# Dual_TPA6120_V0001.net
KiCad netlist of a schematic drawn in EAGLE
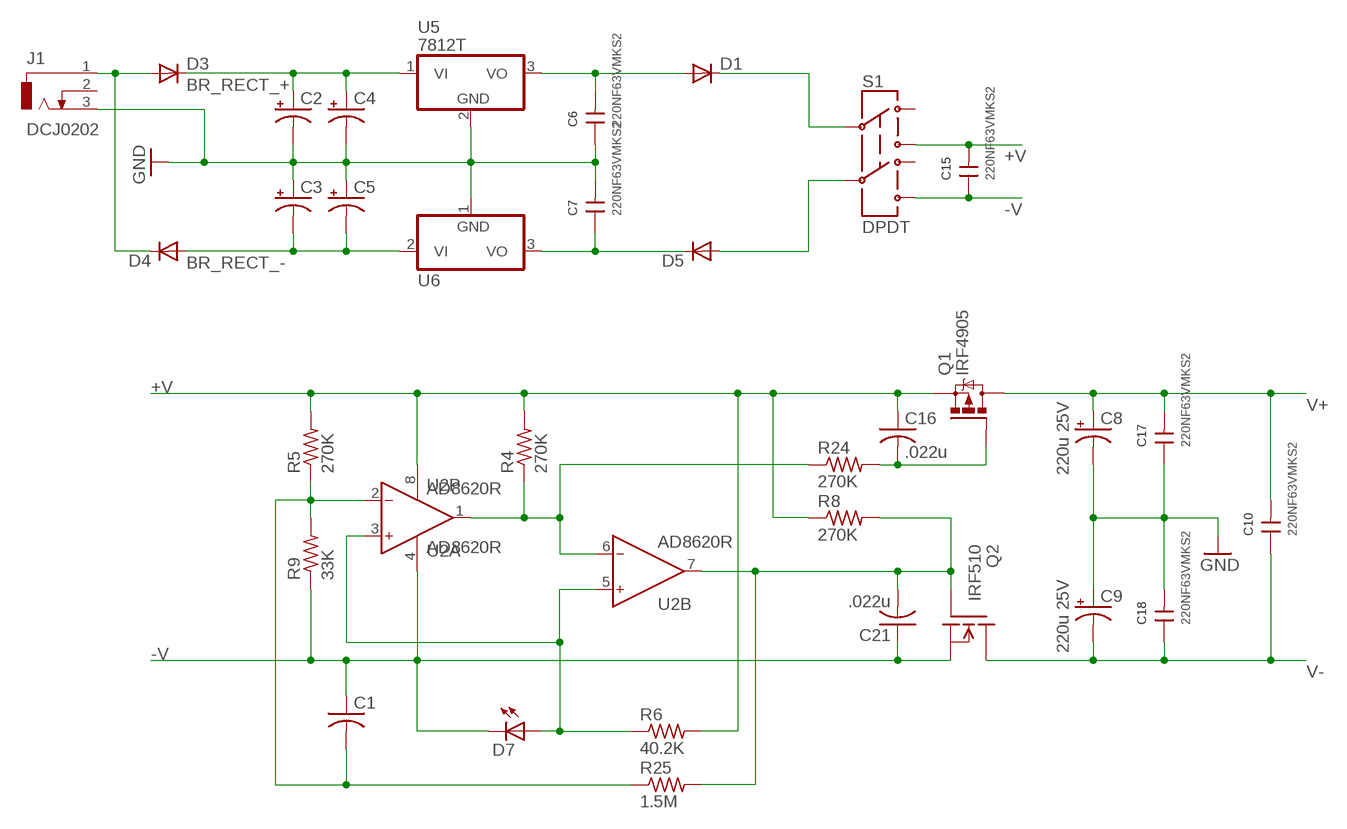
[diagram p0: schematic, sheet 1]
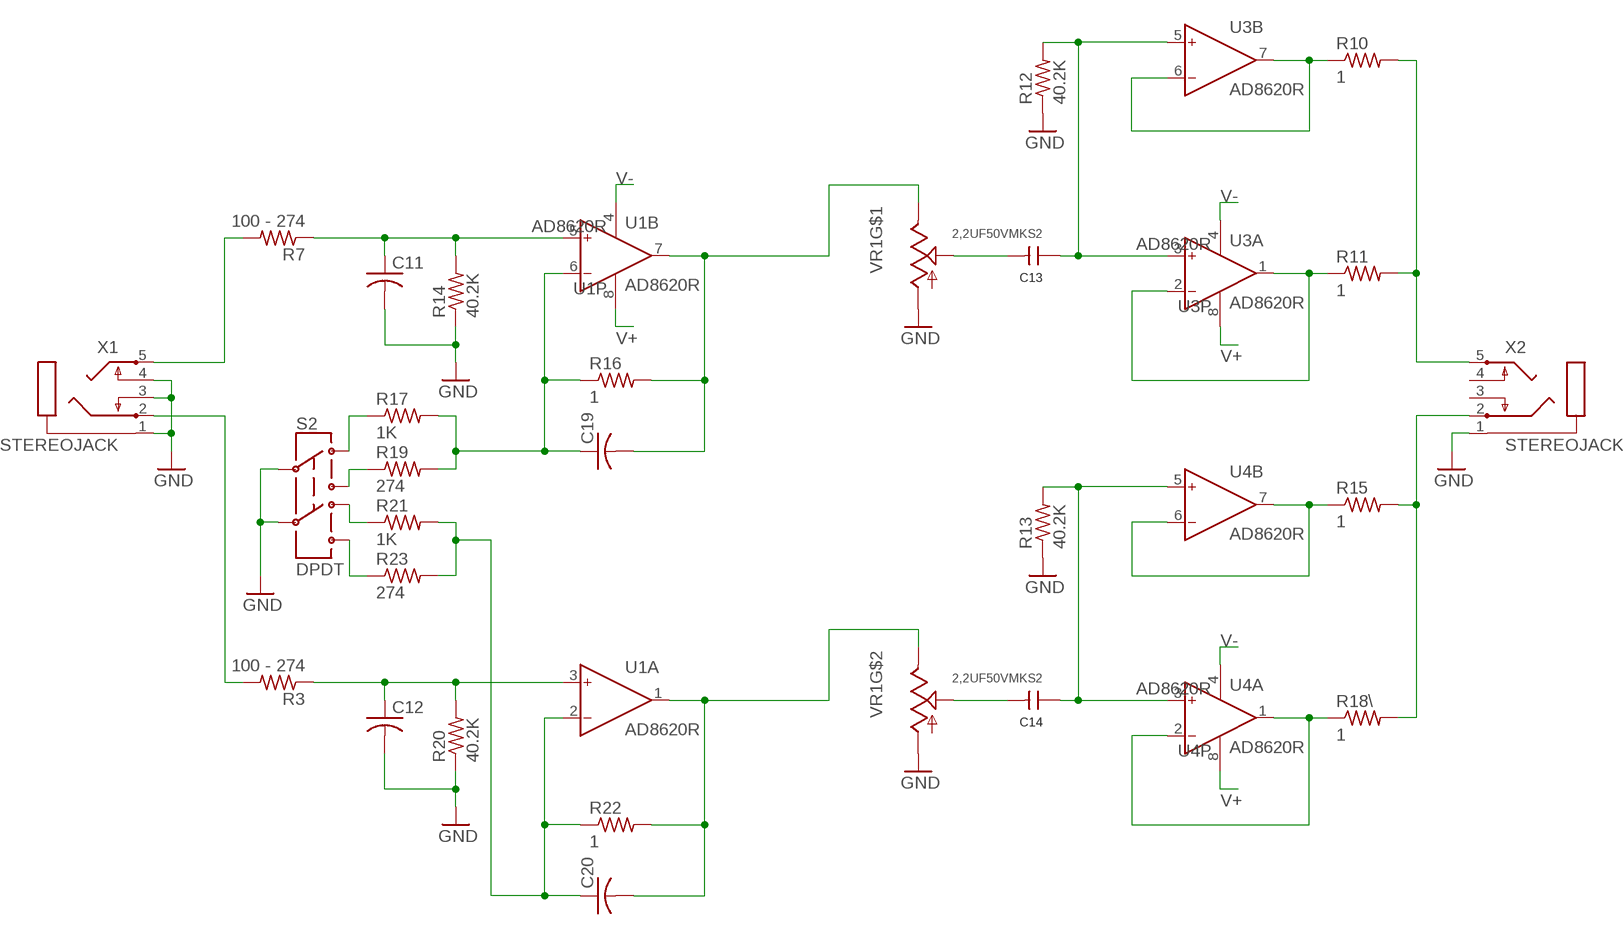
[diagram p1: schematic, sheet 2]

(export (version "E")
  (design (tool "Eeschema 10.0.6"))
  (components
    (comp (ref "C11")
      (value "C-USC0603")
      (footprint "eagle-import:C0603")
      (libsource (lib "eagle-import") (part "C-USC0603"))
    )
    (comp (ref "C12")
      (value "C-USC0603")
      (footprint "eagle-import:C0603")
      (libsource (lib "eagle-import") (part "C-USC0603"))
    )
    (comp (ref "C13")
      (value "2,2UF50VMKS2")
      (footprint "eagle-import:7,2X13,0RM5,0")
      (libsource (lib "eagle-import") (part "2,2UF50VMKS2"))
    )
    (comp (ref "C14")
      (value "2,2UF50VMKS2")
      (footprint "eagle-import:7,2X13,0RM5,0")
      (libsource (lib "eagle-import") (part "2,2UF50VMKS2"))
    )
    (comp (ref "C19")
      (value "C-USC0603")
      (footprint "eagle-import:C0603")
      (libsource (lib "eagle-import") (part "C-USC0603"))
    )
    (comp (ref "C20")
      (value "C-USC0603")
      (footprint "eagle-import:C0603")
      (libsource (lib "eagle-import") (part "C-USC0603"))
    )
    (comp (ref "R3")
      (value "100 - 274")
      (footprint "eagle-import:R1206")
      (libsource (lib "eagle-import") (part "R-US_R1206"))
    )
    (comp (ref "R7")
      (value "100 - 274")
      (footprint "eagle-import:R1206")
      (libsource (lib "eagle-import") (part "R-US_R1206"))
    )
    (comp (ref "R10")
      (value "1")
      (footprint "eagle-import:R1206")
      (libsource (lib "eagle-import") (part "R-US_R1206"))
    )
    (comp (ref "R11")
      (value "1")
      (footprint "eagle-import:R1206")
      (libsource (lib "eagle-import") (part "R-US_R1206"))
    )
    (comp (ref "R12")
      (value "40.2K")
      (footprint "eagle-import:R1206")
      (libsource (lib "eagle-import") (part "R-US_R1206"))
    )
    (comp (ref "R13")
      (value "40.2K")
      (footprint "eagle-import:R1206")
      (libsource (lib "eagle-import") (part "R-US_R1206"))
    )
    (comp (ref "R14")
      (value "40.2K")
      (footprint "eagle-import:R1206")
      (libsource (lib "eagle-import") (part "R-US_R1206"))
    )
    (comp (ref "R15")
      (value "1")
      (footprint "eagle-import:R1206")
      (libsource (lib "eagle-import") (part "R-US_R1206"))
    )
    (comp (ref "R16")
      (value "1")
      (footprint "eagle-import:R1206")
      (libsource (lib "eagle-import") (part "R-US_R1206"))
    )
    (comp (ref "R17")
      (value "1K")
      (footprint "eagle-import:R1206")
      (libsource (lib "eagle-import") (part "R-US_R1206"))
    )
    (comp (ref "R18\\")
      (value "1")
      (footprint "eagle-import:R1206")
      (libsource (lib "eagle-import") (part "R-US_R1206"))
    )
    (comp (ref "R19")
      (value "274")
      (footprint "eagle-import:R1206")
      (libsource (lib "eagle-import") (part "R-US_R1206"))
    )
    (comp (ref "R20")
      (value "40.2K")
      (footprint "eagle-import:R1206")
      (libsource (lib "eagle-import") (part "R-US_R1206"))
    )
    (comp (ref "R21")
      (value "1K")
      (footprint "eagle-import:R1206")
      (libsource (lib "eagle-import") (part "R-US_R1206"))
    )
    (comp (ref "R22")
      (value "1")
      (footprint "eagle-import:R1206")
      (libsource (lib "eagle-import") (part "R-US_R1206"))
    )
    (comp (ref "R23")
      (value "274")
      (footprint "eagle-import:R1206")
      (libsource (lib "eagle-import") (part "R-US_R1206"))
    )
    (comp (ref "S2")
      (value "DPDT")
      (footprint "eagle-import:AYZ0202")
      (libsource (lib "eagle-import") (part "SWITCH-DPDTAYZ0202"))
    )
    (comp (ref "U1")
      (value "AD8620R")
      (footprint "eagle-import:SO8")
      (fields (field (name "MF") "ALTERA CORPORATION") (field (name "MPN") "AD8620ARZ"))
      (libsource (lib "eagle-import") (part "AD8620R"))
    )
    (comp (ref "U3")
      (value "AD8620R")
      (footprint "eagle-import:SO8")
      (fields (field (name "MF") "ALTERA CORPORATION") (field (name "MPN") "AD8620ARZ"))
      (libsource (lib "eagle-import") (part "AD8620R"))
    )
    (comp (ref "U4")
      (value "AD8620R")
      (footprint "eagle-import:SO8")
      (fields (field (name "MF") "ALTERA CORPORATION") (field (name "MPN") "AD8620ARZ"))
      (libsource (lib "eagle-import") (part "AD8620R"))
    )
    (comp (ref "VR1")
      (value "ALPS_BLUE")
      (footprint "eagle-import:ALPS_RK27")
      (libsource (lib "eagle-import") (part "ALPS_BLUE"))
    )
    (comp (ref "X1")
      (value "STEREOJACK")
      (footprint "eagle-import:STX3100")
      (libsource (lib "eagle-import") (part "STEREOJACK"))
    )
    (comp (ref "X2")
      (value "STEREOJACK")
      (footprint "eagle-import:STX3100")
      (libsource (lib "eagle-import") (part "STEREOJACK"))
    )
    (comp (ref "C1")
      (value "C-USC0603")
      (footprint "eagle-import:C0603")
      (libsource (lib "eagle-import") (part "C-USC0603"))
    )
    (comp (ref "C2")
      (value "CPOL-USE7.5-16")
      (footprint "eagle-import:E7,5-16")
      (libsource (lib "eagle-import") (part "CPOL-USE7.5-16"))
    )
    (comp (ref "C3")
      (value "CPOL-USE7.5-16")
      (footprint "eagle-import:E7,5-16")
      (libsource (lib "eagle-import") (part "CPOL-USE7.5-16"))
    )
    (comp (ref "C4")
      (value "CPOL-USE7.5-16")
      (footprint "eagle-import:E7,5-16")
      (libsource (lib "eagle-import") (part "CPOL-USE7.5-16"))
    )
    (comp (ref "C5")
      (value "CPOL-USE7.5-16")
      (footprint "eagle-import:E7,5-16")
      (libsource (lib "eagle-import") (part "CPOL-USE7.5-16"))
    )
    (comp (ref "C6")
      (value "220NF63VMKS2")
      (footprint "eagle-import:3,0X7,5RM5,0")
      (libsource (lib "eagle-import") (part "220NF63VMKS2"))
    )
    (comp (ref "C7")
      (value "220NF63VMKS2")
      (footprint "eagle-import:3,0X7,5RM5,0")
      (libsource (lib "eagle-import") (part "220NF63VMKS2"))
    )
    (comp (ref "C8")
      (value "220u 25V")
      (footprint "eagle-import:E3,5-10")
      (libsource (lib "eagle-import") (part "CPOL-USE3.5-10"))
    )
    (comp (ref "C9")
      (value "220u 25V")
      (footprint "eagle-import:E3,5-10")
      (libsource (lib "eagle-import") (part "CPOL-USE3.5-10"))
    )
    (comp (ref "C10")
      (value "220NF63VMKS2")
      (footprint "eagle-import:3,0X7,5RM5,0")
      (libsource (lib "eagle-import") (part "220NF63VMKS2"))
    )
    (comp (ref "C15")
      (value "220NF63VMKS2")
      (footprint "eagle-import:3,0X7,5RM5,0")
      (libsource (lib "eagle-import") (part "220NF63VMKS2"))
    )
    (comp (ref "C16")
      (value ".022u")
      (footprint "eagle-import:C0603")
      (libsource (lib "eagle-import") (part "C-USC0603"))
    )
    (comp (ref "C17")
      (value "220NF63VMKS2")
      (footprint "eagle-import:3,0X7,5RM5,0")
      (libsource (lib "eagle-import") (part "220NF63VMKS2"))
    )
    (comp (ref "C18")
      (value "220NF63VMKS2")
      (footprint "eagle-import:3,0X7,5RM5,0")
      (libsource (lib "eagle-import") (part "220NF63VMKS2"))
    )
    (comp (ref "C21")
      (value ".022u")
      (footprint "eagle-import:C0603")
      (libsource (lib "eagle-import") (part "C-USC0603"))
    )
    (comp (ref "D1")
      (value "1N5060GP")
      (footprint "eagle-import:DO15-12")
      (libsource (lib "eagle-import") (part "1N5060GP"))
    )
    (comp (ref "D3")
      (value "1N5060GP")
      (footprint "eagle-import:DO15-12")
      (libsource (lib "eagle-import") (part "1N5060GP"))
    )
    (comp (ref "D4")
      (value "1N5060GP")
      (footprint "eagle-import:DO15-12")
      (libsource (lib "eagle-import") (part "1N5060GP"))
    )
    (comp (ref "D5")
      (value "1N5060GP")
      (footprint "eagle-import:DO15-12")
      (libsource (lib "eagle-import") (part "1N5060GP"))
    )
    (comp (ref "D7")
      (value "LED3MM")
      (footprint "eagle-import:LED3MM")
      (libsource (lib "eagle-import") (part "LED3MM"))
    )
    (comp (ref "J1")
      (value "DCJ0202")
      (footprint "eagle-import:DCJ0202")
      (libsource (lib "eagle-import") (part "DCJ0202"))
    )
    (comp (ref "Q1")
      (value "IRF4905")
      (footprint "eagle-import:TO220BH")
      (libsource (lib "eagle-import") (part "IRF4905"))
    )
    (comp (ref "Q2")
      (value "IRF510")
      (footprint "eagle-import:TO220")
      (libsource (lib "eagle-import") (part "IRF510"))
    )
    (comp (ref "R4")
      (value "270K")
      (footprint "eagle-import:R0805")
      (libsource (lib "eagle-import") (part "R-US_R0805"))
    )
    (comp (ref "R5")
      (value "270K")
      (footprint "eagle-import:R0805")
      (libsource (lib "eagle-import") (part "R-US_R0805"))
    )
    (comp (ref "R6")
      (value "40.2K")
      (footprint "eagle-import:R0805")
      (libsource (lib "eagle-import") (part "R-US_R0805"))
    )
    (comp (ref "R8")
      (value "270K")
      (footprint "eagle-import:R0805")
      (libsource (lib "eagle-import") (part "R-US_R0805"))
    )
    (comp (ref "R9")
      (value "33K")
      (footprint "eagle-import:R0805")
      (libsource (lib "eagle-import") (part "R-US_R0805"))
    )
    (comp (ref "R24")
      (value "270K")
      (footprint "eagle-import:R0805")
      (libsource (lib "eagle-import") (part "R-US_R0805"))
    )
    (comp (ref "R25")
      (value "1.5M")
      (footprint "eagle-import:R0805")
      (libsource (lib "eagle-import") (part "R-US_R0805"))
    )
    (comp (ref "S1")
      (value "DPDT")
      (footprint "eagle-import:AYZ0202")
      (libsource (lib "eagle-import") (part "SWITCH-DPDTAYZ0202"))
    )
    (comp (ref "U2")
      (value "AD8620R")
      (footprint "eagle-import:SO8")
      (fields (field (name "MF") "ALTERA CORPORATION") (field (name "MPN") "AD8620ARZ"))
      (libsource (lib "eagle-import") (part "AD8620R"))
    )
    (comp (ref "U5")
      (value "7812T")
      (footprint "eagle-import:TO220H")
      (libsource (lib "eagle-import") (part "78T12"))
    )
    (comp (ref "U6")
      (value "7912T")
      (footprint "eagle-import:TO220H")
      (libsource (lib "eagle-import") (part "79T12"))
    )
  )
  (nets
    (net (code "1") (name "+V") (class "Default")
      (node (ref "C15") (pin "2") (pinfunction "2_2") (pintype "passive"))
      (node (ref "C16") (pin "1") (pinfunction "1_1") (pintype "passive"))
      (node (ref "Q1") (pin "S") (pinfunction "S_S") (pintype "passive"))
      (node (ref "R4") (pin "2") (pinfunction "2_2") (pintype "passive"))
      (node (ref "R5") (pin "2") (pinfunction "2_2") (pintype "passive"))
      (node (ref "R6") (pin "2") (pinfunction "2_2") (pintype "passive"))
      (node (ref "R8") (pin "1") (pinfunction "1_1") (pintype "passive"))
      (node (ref "S1") (pin "3") (pinfunction "3_3") (pintype "bidirectional"))
      (node (ref "U2") (pin "8") (pinfunction "V+_8") (pintype "power_in"))
    )
    (net (code "2") (name "-V") (class "Default")
      (node (ref "C1") (pin "1") (pinfunction "1_1") (pintype "passive"))
      (node (ref "C15") (pin "1") (pinfunction "1_1") (pintype "passive"))
      (node (ref "C21") (pin "1") (pinfunction "1_1") (pintype "passive"))
      (node (ref "D7") (pin "K") (pinfunction "C_K") (pintype "passive"))
      (node (ref "Q2") (pin "3") (pinfunction "S_3") (pintype "passive"))
      (node (ref "R9") (pin "1") (pinfunction "1_1") (pintype "passive"))
      (node (ref "S1") (pin "6") (pinfunction "6_6") (pintype "bidirectional"))
      (node (ref "U2") (pin "4") (pinfunction "V-_4") (pintype "power_in"))
    )
    (net (code "3") (name "BR_RECT_+") (class "Default")
      (node (ref "C2") (pin "+") (pinfunction "+_+") (pintype "passive"))
      (node (ref "C4") (pin "+") (pinfunction "+_+") (pintype "passive"))
      (node (ref "D3") (pin "C") (pinfunction "C_C") (pintype "passive"))
      (node (ref "U5") (pin "1") (pinfunction "VI_1") (pintype "input"))
    )
    (net (code "4") (name "BR_RECT_-") (class "Default")
      (node (ref "C3") (pin "-") (pinfunction "-_-") (pintype "passive"))
      (node (ref "C5") (pin "-") (pinfunction "-_-") (pintype "passive"))
      (node (ref "D4") (pin "A") (pinfunction "A_A") (pintype "passive"))
      (node (ref "U6") (pin "2") (pinfunction "VI_2") (pintype "input"))
    )
    (net (code "5") (name "GND") (class "Default")
      (node (ref "C11") (pin "2") (pinfunction "2_2") (pintype "passive"))
      (node (ref "C12") (pin "2") (pinfunction "2_2") (pintype "passive"))
      (node (ref "C17") (pin "1") (pinfunction "1_1") (pintype "passive"))
      (node (ref "C18") (pin "2") (pinfunction "2_2") (pintype "passive"))
      (node (ref "C2") (pin "-") (pinfunction "-_-") (pintype "passive"))
      (node (ref "C3") (pin "+") (pinfunction "+_+") (pintype "passive"))
      (node (ref "C4") (pin "-") (pinfunction "-_-") (pintype "passive"))
      (node (ref "C5") (pin "+") (pinfunction "+_+") (pintype "passive"))
      (node (ref "C6") (pin "1") (pinfunction "1_1") (pintype "passive"))
      (node (ref "C7") (pin "2") (pinfunction "2_2") (pintype "passive"))
      (node (ref "C8") (pin "-") (pinfunction "-_-") (pintype "passive"))
      (node (ref "C9") (pin "+") (pinfunction "+_+") (pintype "passive"))
      (node (ref "J1") (pin "3") (pinfunction "3_3") (pintype "passive"))
      (node (ref "R12") (pin "1") (pinfunction "1_1") (pintype "passive"))
      (node (ref "R13") (pin "1") (pinfunction "1_1") (pintype "passive"))
      (node (ref "R14") (pin "1") (pinfunction "1_1") (pintype "passive"))
      (node (ref "R20") (pin "1") (pinfunction "1_1") (pintype "passive"))
      (node (ref "S2") (pin "2") (pinfunction "2_2") (pintype "bidirectional"))
      (node (ref "S2") (pin "5") (pinfunction "5_5") (pintype "bidirectional"))
      (node (ref "U5") (pin "2") (pinfunction "GND_2") (pintype "passive"))
      (node (ref "U6") (pin "1") (pinfunction "GND_1") (pintype "passive"))
      (node (ref "VR1") (pin "G1") (pinfunction "1_G1") (pintype "passive"))
      (node (ref "VR1") (pin "G2") (pinfunction "1_G2") (pintype "passive"))
      (node (ref "X1") (pin "1") (pinfunction "1_1") (pintype "passive"))
      (node (ref "X1") (pin "3") (pinfunction "3_3") (pintype "passive"))
      (node (ref "X1") (pin "4") (pinfunction "4_4") (pintype "passive"))
      (node (ref "X2") (pin "1") (pinfunction "1_1") (pintype "passive"))
    )
    (net (code "6") (name "Net-(C16-Pad2)") (class "Default")
      (node (ref "C16") (pin "2") (pinfunction "2_2") (pintype "passive"))
      (node (ref "Q1") (pin "G") (pinfunction "G_G") (pintype "passive"))
      (node (ref "R24") (pin "2") (pinfunction "2_2") (pintype "passive"))
    )
    (net (code "7") (name "Net-(D1-PadC)") (class "Default")
      (node (ref "D1") (pin "C") (pinfunction "C_C") (pintype "passive"))
      (node (ref "S1") (pin "2") (pinfunction "2_2") (pintype "bidirectional"))
    )
    (net (code "8") (name "Net-(D3-PadA)") (class "Default")
      (node (ref "D3") (pin "A") (pinfunction "A_A") (pintype "passive"))
      (node (ref "D4") (pin "C") (pinfunction "C_C") (pintype "passive"))
      (node (ref "J1") (pin "1") (pinfunction "1_1") (pintype "passive"))
    )
    (net (code "9") (name "Net-(D5-PadA)") (class "Default")
      (node (ref "D5") (pin "A") (pinfunction "A_A") (pintype "passive"))
      (node (ref "S1") (pin "5") (pinfunction "5_5") (pintype "bidirectional"))
    )
    (net (code "10") (name "Net-(Q2-G)") (class "Default")
      (node (ref "C21") (pin "2") (pinfunction "2_2") (pintype "passive"))
      (node (ref "Q2") (pin "1") (pinfunction "G_1") (pintype "passive"))
      (node (ref "R25") (pin "2") (pinfunction "2_2") (pintype "passive"))
      (node (ref "R8") (pin "2") (pinfunction "2_2") (pintype "passive"))
      (node (ref "U2") (pin "7") (pinfunction "OUT_7") (pintype "output"))
    )
    (net (code "11") (name "Net-(R3-Pad2)") (class "Default")
      (node (ref "R3") (pin "2") (pinfunction "2_2") (pintype "passive"))
      (node (ref "X1") (pin "2") (pinfunction "2_2") (pintype "passive"))
    )
    (net (code "12") (name "Net-(R7-Pad2)") (class "Default")
      (node (ref "R7") (pin "2") (pinfunction "2_2") (pintype "passive"))
      (node (ref "X1") (pin "5") (pinfunction "5_5") (pintype "passive"))
    )
    (net (code "13") (name "Net-(R10-Pad2)") (class "Default")
      (node (ref "R10") (pin "2") (pinfunction "2_2") (pintype "passive"))
      (node (ref "R11") (pin "2") (pinfunction "2_2") (pintype "passive"))
      (node (ref "X2") (pin "5") (pinfunction "5_5") (pintype "passive"))
    )
    (net (code "14") (name "Net-(R15-Pad2)") (class "Default")
      (node (ref "R15") (pin "2") (pinfunction "2_2") (pintype "passive"))
      (node (ref "R18\\") (pin "2") (pinfunction "2_2") (pintype "passive"))
      (node (ref "X2") (pin "2") (pinfunction "2_2") (pintype "passive"))
    )
    (net (code "15") (name "Net-(R17-Pad1)") (class "Default")
      (node (ref "R17") (pin "1") (pinfunction "1_1") (pintype "passive"))
      (node (ref "S2") (pin "1") (pinfunction "1_1") (pintype "bidirectional"))
    )
    (net (code "16") (name "Net-(R19-Pad1)") (class "Default")
      (node (ref "R19") (pin "1") (pinfunction "1_1") (pintype "passive"))
      (node (ref "S2") (pin "3") (pinfunction "3_3") (pintype "bidirectional"))
    )
    (net (code "17") (name "Net-(R21-Pad1)") (class "Default")
      (node (ref "R21") (pin "1") (pinfunction "1_1") (pintype "passive"))
      (node (ref "S2") (pin "4") (pinfunction "4_4") (pintype "bidirectional"))
    )
    (net (code "18") (name "Net-(R23-Pad1)") (class "Default")
      (node (ref "R23") (pin "1") (pinfunction "1_1") (pintype "passive"))
      (node (ref "S2") (pin "6") (pinfunction "6_6") (pintype "bidirectional"))
    )
    (net (code "19") (name "Net-(U1A-IN+)") (class "Default")
      (node (ref "C12") (pin "1") (pinfunction "1_1") (pintype "passive"))
      (node (ref "R20") (pin "2") (pinfunction "2_2") (pintype "passive"))
      (node (ref "R3") (pin "1") (pinfunction "1_1") (pintype "passive"))
      (node (ref "U1") (pin "3") (pinfunction "IN+_3") (pintype "input"))
    )
    (net (code "20") (name "Net-(U1A-IN-)") (class "Default")
      (node (ref "C20") (pin "1") (pinfunction "1_1") (pintype "passive"))
      (node (ref "R21") (pin "2") (pinfunction "2_2") (pintype "passive"))
      (node (ref "R22") (pin "1") (pinfunction "1_1") (pintype "passive"))
      (node (ref "R23") (pin "2") (pinfunction "2_2") (pintype "passive"))
      (node (ref "U1") (pin "2") (pinfunction "IN-_2") (pintype "input"))
    )
    (net (code "21") (name "Net-(U1A-OUT)") (class "Default")
      (node (ref "C20") (pin "2") (pinfunction "2_2") (pintype "passive"))
      (node (ref "R22") (pin "2") (pinfunction "2_2") (pintype "passive"))
      (node (ref "U1") (pin "1") (pinfunction "OUT_1") (pintype "output"))
      (node (ref "VR1") (pin "I2") (pinfunction "3_I2") (pintype "passive"))
    )
    (net (code "22") (name "Net-(U1B-IN+)") (class "Default")
      (node (ref "C11") (pin "1") (pinfunction "1_1") (pintype "passive"))
      (node (ref "R14") (pin "2") (pinfunction "2_2") (pintype "passive"))
      (node (ref "R7") (pin "1") (pinfunction "1_1") (pintype "passive"))
      (node (ref "U1") (pin "5") (pinfunction "IN+_5") (pintype "input"))
    )
    (net (code "23") (name "Net-(U1B-IN-)") (class "Default")
      (node (ref "C19") (pin "1") (pinfunction "1_1") (pintype "passive"))
      (node (ref "R16") (pin "1") (pinfunction "1_1") (pintype "passive"))
      (node (ref "R17") (pin "2") (pinfunction "2_2") (pintype "passive"))
      (node (ref "R19") (pin "2") (pinfunction "2_2") (pintype "passive"))
      (node (ref "U1") (pin "6") (pinfunction "IN-_6") (pintype "input"))
    )
    (net (code "24") (name "Net-(U1B-OUT)") (class "Default")
      (node (ref "C19") (pin "2") (pinfunction "2_2") (pintype "passive"))
      (node (ref "R16") (pin "2") (pinfunction "2_2") (pintype "passive"))
      (node (ref "U1") (pin "7") (pinfunction "OUT_7") (pintype "output"))
      (node (ref "VR1") (pin "I1") (pinfunction "3_I1") (pintype "passive"))
    )
    (net (code "25") (name "Net-(U2A-IN+)") (class "Default")
      (node (ref "D7") (pin "A") (pinfunction "A_A") (pintype "passive"))
      (node (ref "R6") (pin "1") (pinfunction "1_1") (pintype "passive"))
      (node (ref "U2") (pin "3") (pinfunction "IN+_3") (pintype "input"))
      (node (ref "U2") (pin "5") (pinfunction "IN+_5") (pintype "input"))
    )
    (net (code "26") (name "Net-(U2A-IN-)") (class "Default")
      (node (ref "C1") (pin "2") (pinfunction "2_2") (pintype "passive"))
      (node (ref "R25") (pin "1") (pinfunction "1_1") (pintype "passive"))
      (node (ref "R5") (pin "1") (pinfunction "1_1") (pintype "passive"))
      (node (ref "R9") (pin "2") (pinfunction "2_2") (pintype "passive"))
      (node (ref "U2") (pin "2") (pinfunction "IN-_2") (pintype "input"))
    )
    (net (code "27") (name "Net-(U2A-OUT)") (class "Default")
      (node (ref "R24") (pin "1") (pinfunction "1_1") (pintype "passive"))
      (node (ref "R4") (pin "1") (pinfunction "1_1") (pintype "passive"))
      (node (ref "U2") (pin "1") (pinfunction "OUT_1") (pintype "output"))
      (node (ref "U2") (pin "6") (pinfunction "IN-_6") (pintype "input"))
    )
    (net (code "28") (name "Net-(U3A-IN+)") (class "Default")
      (node (ref "C13") (pin "1") (pinfunction "1_1") (pintype "passive"))
      (node (ref "R12") (pin "2") (pinfunction "2_2") (pintype "passive"))
      (node (ref "U3") (pin "3") (pinfunction "IN+_3") (pintype "input"))
      (node (ref "U3") (pin "5") (pinfunction "IN+_5") (pintype "input"))
    )
    (net (code "29") (name "Net-(U3A-IN-)") (class "Default")
      (node (ref "R11") (pin "1") (pinfunction "1_1") (pintype "passive"))
      (node (ref "U3") (pin "1") (pinfunction "OUT_1") (pintype "output"))
      (node (ref "U3") (pin "2") (pinfunction "IN-_2") (pintype "input"))
    )
    (net (code "30") (name "Net-(U3B-IN-)") (class "Default")
      (node (ref "R10") (pin "1") (pinfunction "1_1") (pintype "passive"))
      (node (ref "U3") (pin "6") (pinfunction "IN-_6") (pintype "input"))
      (node (ref "U3") (pin "7") (pinfunction "OUT_7") (pintype "output"))
    )
    (net (code "31") (name "Net-(U4A-IN+)") (class "Default")
      (node (ref "C14") (pin "1") (pinfunction "1_1") (pintype "passive"))
      (node (ref "R13") (pin "2") (pinfunction "2_2") (pintype "passive"))
      (node (ref "U4") (pin "3") (pinfunction "IN+_3") (pintype "input"))
      (node (ref "U4") (pin "5") (pinfunction "IN+_5") (pintype "input"))
    )
    (net (code "32") (name "Net-(U4A-IN-)") (class "Default")
      (node (ref "R18\\") (pin "1") (pinfunction "1_1") (pintype "passive"))
      (node (ref "U4") (pin "1") (pinfunction "OUT_1") (pintype "output"))
      (node (ref "U4") (pin "2") (pinfunction "IN-_2") (pintype "input"))
    )
    (net (code "33") (name "Net-(U4B-IN-)") (class "Default")
      (node (ref "R15") (pin "1") (pinfunction "1_1") (pintype "passive"))
      (node (ref "U4") (pin "6") (pinfunction "IN-_6") (pintype "input"))
      (node (ref "U4") (pin "7") (pinfunction "OUT_7") (pintype "output"))
    )
    (net (code "34") (name "Net-(U5-VO)") (class "Default")
      (node (ref "C6") (pin "2") (pinfunction "2_2") (pintype "passive"))
      (node (ref "D1") (pin "A") (pinfunction "A_A") (pintype "passive"))
      (node (ref "U5") (pin "3") (pinfunction "VO_3") (pintype "passive"))
    )
    (net (code "35") (name "Net-(U6-VO)") (class "Default")
      (node (ref "C7") (pin "1") (pinfunction "1_1") (pintype "passive"))
      (node (ref "D5") (pin "C") (pinfunction "C_C") (pintype "passive"))
      (node (ref "U6") (pin "3") (pinfunction "VO_3") (pintype "passive"))
    )
    (net (code "36") (name "Net-(VR1A-2)") (class "Default")
      (node (ref "C13") (pin "2") (pinfunction "2_2") (pintype "passive"))
      (node (ref "VR1") (pin "O1") (pinfunction "2_O1") (pintype "passive"))
    )
    (net (code "37") (name "Net-(VR1B-2)") (class "Default")
      (node (ref "C14") (pin "2") (pinfunction "2_2") (pintype "passive"))
      (node (ref "VR1") (pin "O2") (pinfunction "2_O2") (pintype "passive"))
    )
    (net (code "38") (name "V+") (class "Default")
      (node (ref "C10") (pin "2") (pinfunction "2_2") (pintype "passive"))
      (node (ref "C17") (pin "2") (pinfunction "2_2") (pintype "passive"))
      (node (ref "C8") (pin "+") (pinfunction "+_+") (pintype "passive"))
      (node (ref "Q1") (pin "D") (pinfunction "D_D") (pintype "passive"))
      (node (ref "U1") (pin "8") (pinfunction "V+_8") (pintype "power_in"))
      (node (ref "U3") (pin "8") (pinfunction "V+_8") (pintype "power_in"))
      (node (ref "U4") (pin "8") (pinfunction "V+_8") (pintype "power_in"))
    )
    (net (code "39") (name "V-") (class "Default")
      (node (ref "C10") (pin "1") (pinfunction "1_1") (pintype "passive"))
      (node (ref "C18") (pin "1") (pinfunction "1_1") (pintype "passive"))
      (node (ref "C9") (pin "-") (pinfunction "-_-") (pintype "passive"))
      (node (ref "Q2") (pin "2") (pinfunction "D_2") (pintype "passive"))
      (node (ref "U1") (pin "4") (pinfunction "V-_4") (pintype "power_in"))
      (node (ref "U3") (pin "4") (pinfunction "V-_4") (pintype "power_in"))
      (node (ref "U4") (pin "4") (pinfunction "V-_4") (pintype "power_in"))
    )
    (net (code "40") (name "unconnected-(J1-Pad2)") (class "Default")
      (node (ref "J1") (pin "2") (pinfunction "2_2") (pintype "passive"))
    )
    (net (code "41") (name "unconnected-(S1-Pad1)") (class "Default")
      (node (ref "S1") (pin "1") (pinfunction "1_1") (pintype "bidirectional"))
    )
    (net (code "42") (name "unconnected-(S1-Pad4)") (class "Default")
      (node (ref "S1") (pin "4") (pinfunction "4_4") (pintype "bidirectional"))
    )
    (net (code "43") (name "unconnected-(X2-Pad3)") (class "Default")
      (node (ref "X2") (pin "3") (pinfunction "3_3") (pintype "passive"))
    )
    (net (code "44") (name "unconnected-(X2-Pad4)") (class "Default")
      (node (ref "X2") (pin "4") (pinfunction "4_4") (pintype "passive"))
    )
  )
)
